# Conveyor_Limit_Switch.net
KiCad netlist of a schematic drawn in EAGLE
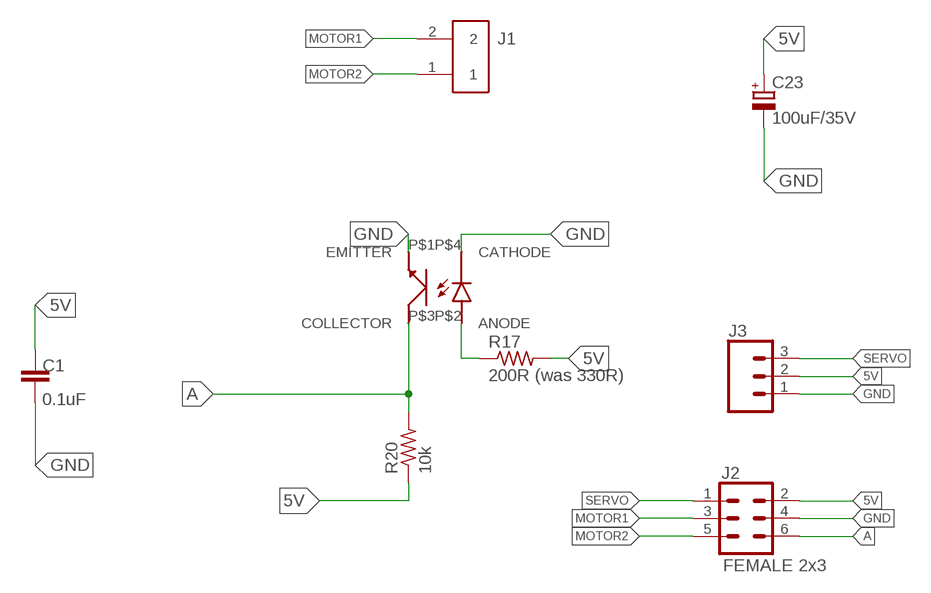
[diagram p0: schematic, sheet 1]

(export (version "E")
  (design (tool "Eeschema 10.0.6"))
  (components
    (comp (ref "C1")
      (value "0.1uF")
      (footprint "eagle-import:CAP_0603")
      (libsource (lib "eagle-import") (part "CAP_0603"))
    )
    (comp (ref "C23")
      (value "100uF/35V")
      (footprint "eagle-import:153CLV-0605")
      (libsource (lib "eagle-import") (part "CPOL-EU153CLV-0605"))
    )
    (comp (ref "J1")
      (value "S2B-PH-SM4-TB(LF)(SN)")
      (footprint "eagle-import:S2B-PH-SM4-TB")
      (fields (field (name "RS_PART_NUMBER") "6881353P"))
      (libsource (lib "eagle-import") (part "S2B-PH-SM4-TB(LF)(SN)"))
    )
    (comp (ref "J2")
      (value "FEMALE 2x3")
      (footprint "eagle-import:2X3")
      (libsource (lib "eagle-import") (part "CONN_03X2FEMALE"))
    )
    (comp (ref "J3")
      (value "CONN_03")
      (footprint "eagle-import:1X03")
      (libsource (lib "eagle-import") (part "CONN_03"))
    )
    (comp (ref "R17")
      (value "200R (was 330R)")
      (footprint "eagle-import:RESISTOR_0603")
      (libsource (lib "eagle-import") (part "RESISTOR_0603"))
    )
    (comp (ref "R20")
      (value "10k")
      (footprint "eagle-import:RESISTOR_0603")
      (libsource (lib "eagle-import") (part "RESISTOR_0603"))
    )
    (comp (ref "U$2")
      (value "IR_VCNT2020")
      (footprint "eagle-import:IR_VCNT2020")
      (libsource (lib "eagle-import") (part "IR_VCNT2020"))
    )
  )
  (nets
    (net (code "1") (name "5V") (class "Default")
      (node (ref "C1") (pin "1") (pinfunction "1_1") (pintype "passive"))
      (node (ref "C23") (pin "+") (pinfunction "+_+") (pintype "passive"))
      (node (ref "J2") (pin "2") (pinfunction "2_2") (pintype "bidirectional"))
      (node (ref "J3") (pin "2") (pinfunction "2_2") (pintype "passive"))
      (node (ref "R17") (pin "2") (pinfunction "2_2") (pintype "passive"))
      (node (ref "R20") (pin "1") (pinfunction "1_1") (pintype "passive"))
    )
    (net (code "2") (name "A") (class "Default")
      (node (ref "J2") (pin "6") (pinfunction "6_6") (pintype "bidirectional"))
      (node (ref "R20") (pin "2") (pinfunction "2_2") (pintype "passive"))
      (node (ref "U$2") (pin "P$3") (pinfunction "COLLECTOR_P$3") (pintype "bidirectional"))
    )
    (net (code "3") (name "GND") (class "Default")
      (node (ref "C1") (pin "2") (pinfunction "2_2") (pintype "passive"))
      (node (ref "C23") (pin "-") (pinfunction "-_-") (pintype "passive"))
      (node (ref "J2") (pin "4") (pinfunction "4_4") (pintype "bidirectional"))
      (node (ref "J3") (pin "1") (pinfunction "1_1") (pintype "passive"))
      (node (ref "U$2") (pin "P$1") (pinfunction "EMITTER_P$1") (pintype "bidirectional"))
      (node (ref "U$2") (pin "P$4") (pinfunction "CATHODE_P$4") (pintype "bidirectional"))
    )
    (net (code "4") (name "MOTOR1") (class "Default")
      (node (ref "J1") (pin "2") (pinfunction "2_2") (pintype "bidirectional"))
      (node (ref "J2") (pin "3") (pinfunction "3_3") (pintype "bidirectional"))
    )
    (net (code "5") (name "MOTOR2") (class "Default")
      (node (ref "J1") (pin "1") (pinfunction "1_1") (pintype "bidirectional"))
      (node (ref "J2") (pin "5") (pinfunction "5_5") (pintype "bidirectional"))
    )
    (net (code "6") (name "Net-(U$2-ANODE)") (class "Default")
      (node (ref "R17") (pin "1") (pinfunction "1_1") (pintype "passive"))
      (node (ref "U$2") (pin "P$2") (pinfunction "ANODE_P$2") (pintype "bidirectional"))
    )
    (net (code "7") (name "SERVO") (class "Default")
      (node (ref "J2") (pin "1") (pinfunction "1_1") (pintype "bidirectional"))
      (node (ref "J3") (pin "3") (pinfunction "3_3") (pintype "passive"))
    )
  )
)
